# Nakuja_Remix_4.net
KiCad netlist of a schematic drawn in EasyEDA
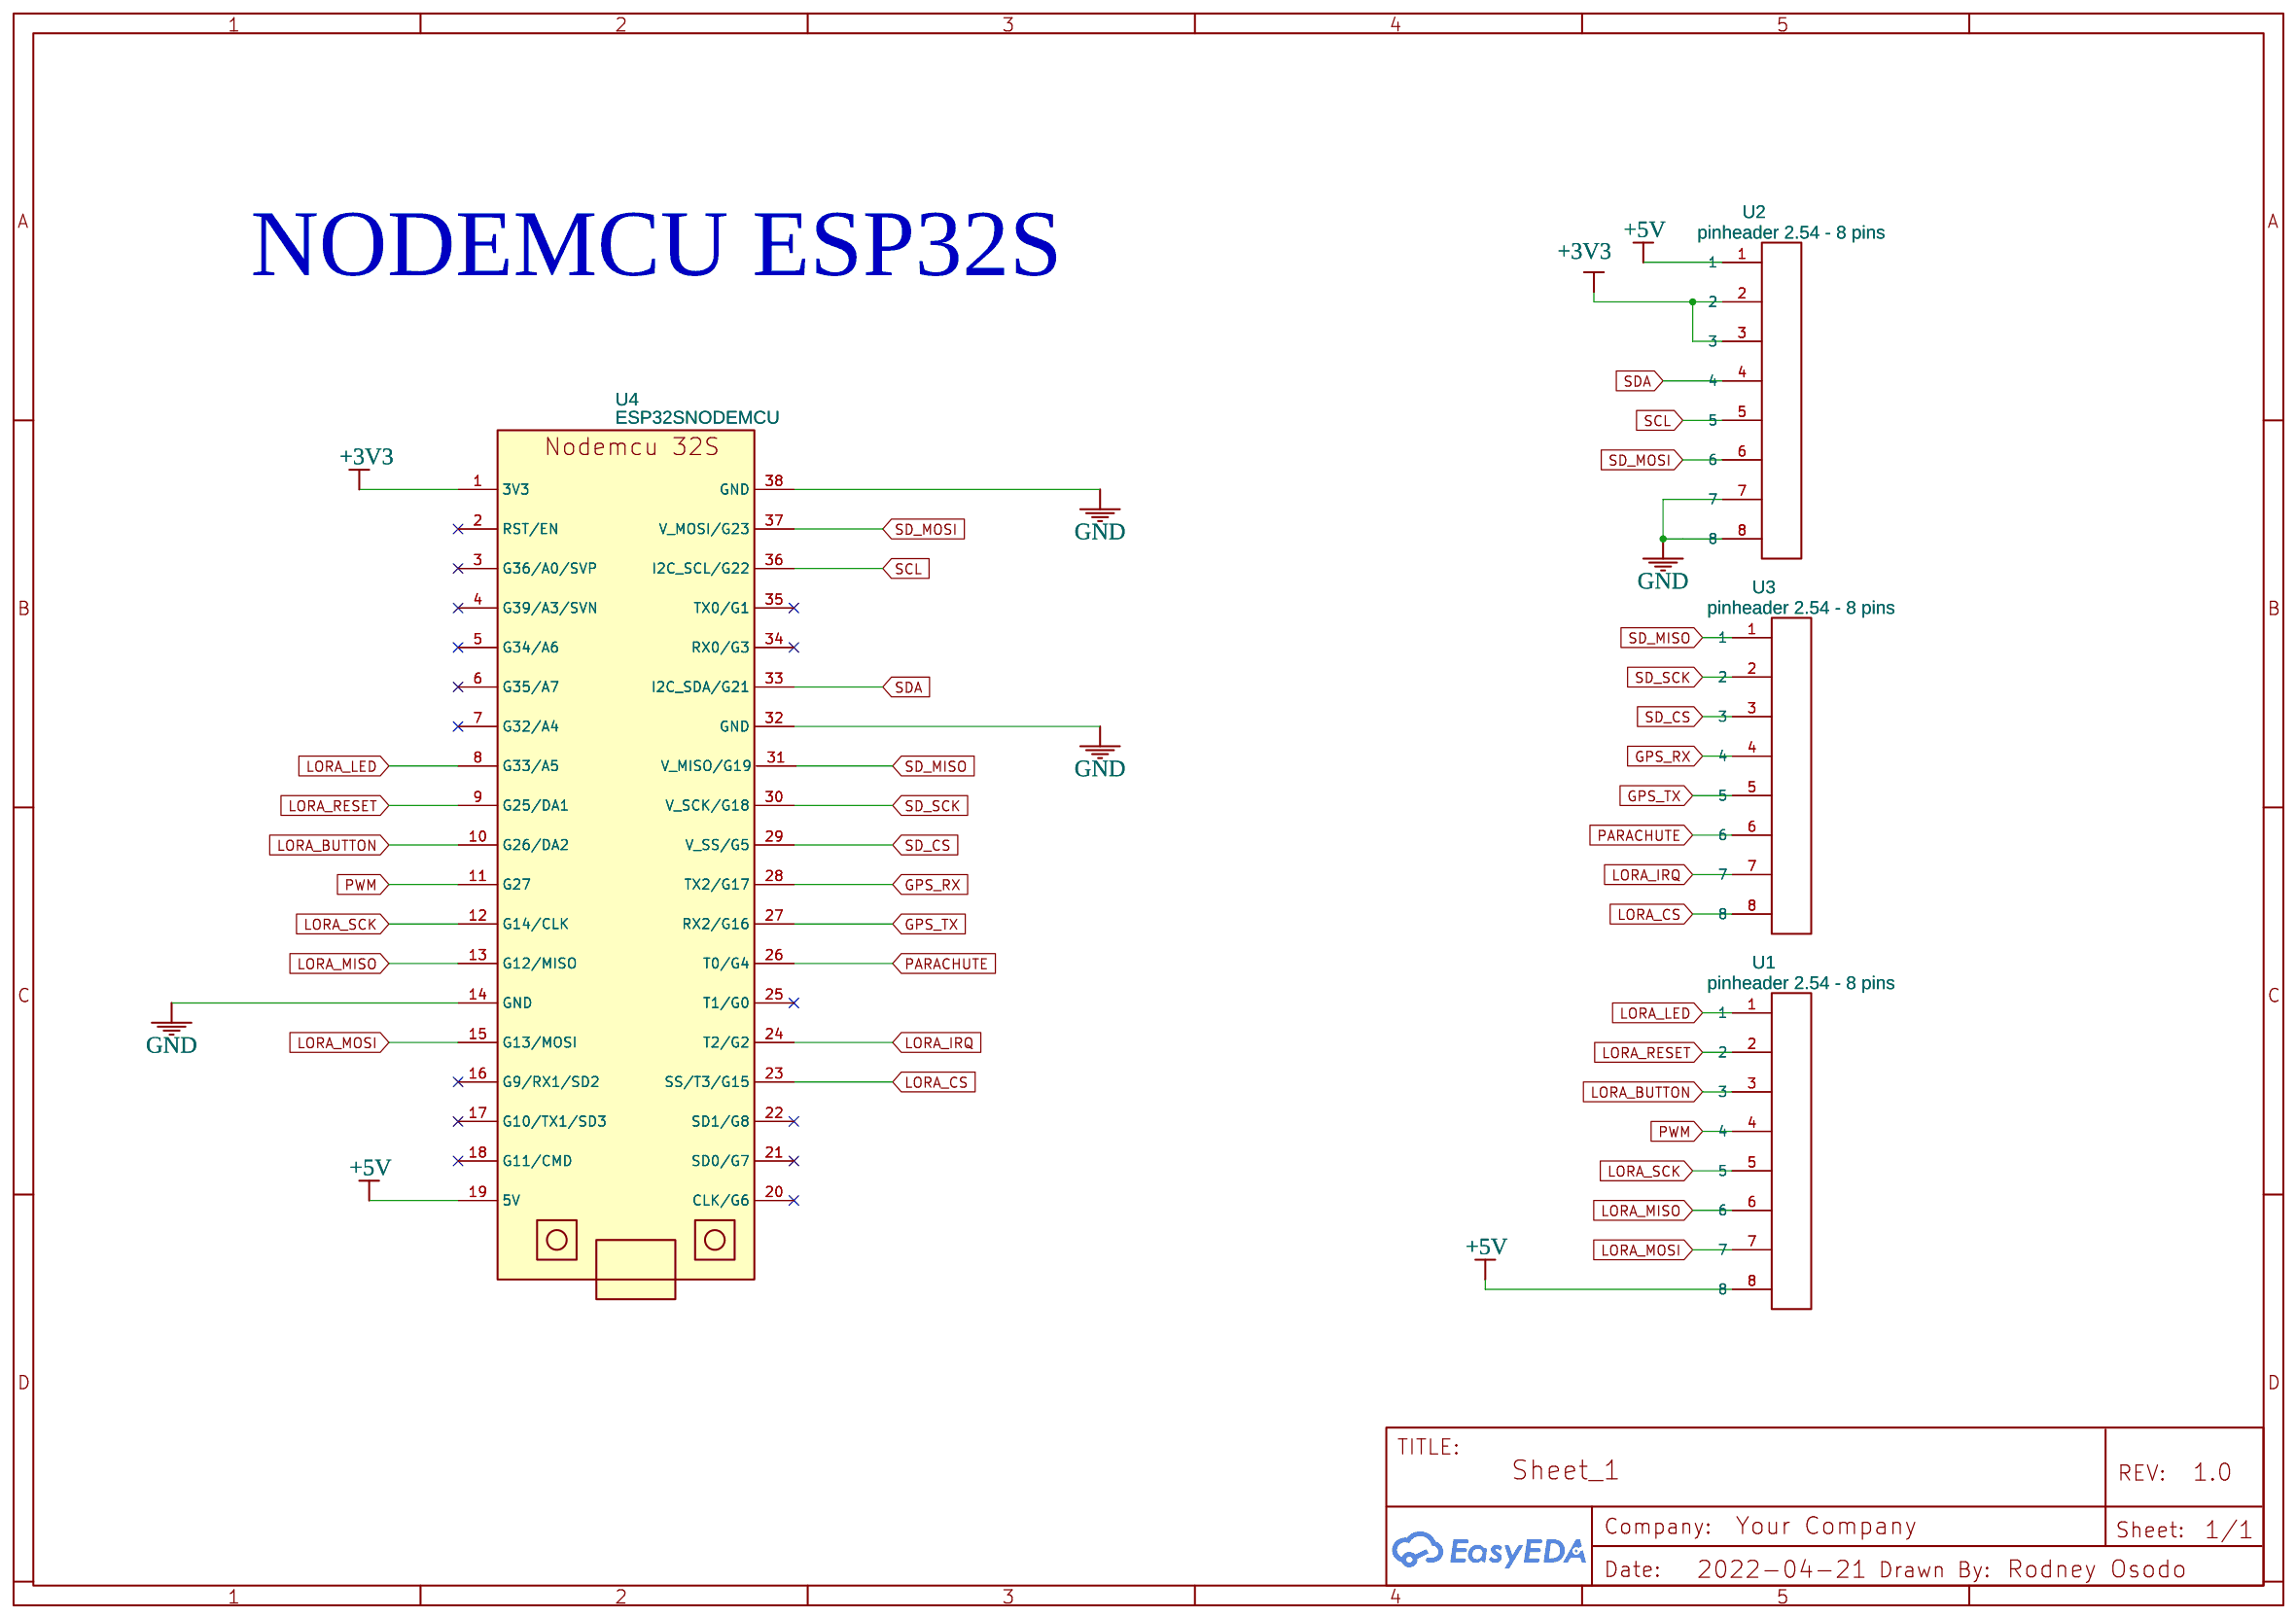
[diagram p0: schematic sheet]

(export (version "E")
  (design (tool "Eeschema 10.0.6"))
  (components
    (comp (ref "U1") (value "pinheader 2.54 - 8 pins") (libsource (lib "") (part "pinheader 2.54 - 8 pins")))
    (comp (ref "U2") (value "pinheader 2.54 - 8 pins") (libsource (lib "") (part "pinheader 2.54 - 8 pins")))
    (comp (ref "U3") (value "pinheader 2.54 - 8 pins") (libsource (lib "") (part "pinheader 2.54 - 8 pins")))
    (comp (ref "U4")
      (value "ESP32SNODEMCU")
      (fields (field (name "BOM_Manufacturer Part") "Nodemcu esp32"))
      (libsource (lib "") (part "ESP32SNODEMCU"))
    )
  )
  (nets
    (net (code "1") (name "+3V3") (class "Default")
      (node (ref "U2") (pin "2") (pinfunction "2_2") (pintype "unspecified"))
      (node (ref "U2") (pin "3") (pinfunction "3_3") (pintype "unspecified"))
      (node (ref "U4") (pin "1") (pinfunction "3V3_1") (pintype "passive"))
    )
    (net (code "2") (name "+5V") (class "Default")
      (node (ref "U1") (pin "8") (pinfunction "8_8") (pintype "unspecified"))
      (node (ref "U2") (pin "1") (pinfunction "1_1") (pintype "unspecified"))
      (node (ref "U4") (pin "19") (pinfunction "5V_19") (pintype "passive"))
    )
    (net (code "3") (name "GND") (class "Default")
      (node (ref "U2") (pin "7") (pinfunction "7_7") (pintype "unspecified"))
      (node (ref "U2") (pin "8") (pinfunction "8_8") (pintype "unspecified"))
      (node (ref "U4") (pin "14") (pinfunction "GND_14") (pintype "passive"))
      (node (ref "U4") (pin "32") (pinfunction "GND_32") (pintype "passive"))
      (node (ref "U4") (pin "38") (pinfunction "GND_38") (pintype "passive"))
    )
    (net (code "4") (name "GPS_RX") (class "Default")
      (node (ref "U3") (pin "4") (pinfunction "4_4") (pintype "unspecified"))
      (node (ref "U4") (pin "28") (pinfunction "TX2/G17_28") (pintype "bidirectional"))
    )
    (net (code "5") (name "GPS_TX") (class "Default")
      (node (ref "U3") (pin "5") (pinfunction "5_5") (pintype "unspecified"))
      (node (ref "U4") (pin "27") (pinfunction "RX2/G16_27") (pintype "bidirectional"))
    )
    (net (code "6") (name "LORA_BUTTON") (class "Default")
      (node (ref "U1") (pin "3") (pinfunction "3_3") (pintype "unspecified"))
      (node (ref "U4") (pin "10") (pinfunction "G26/DA2_10") (pintype "bidirectional"))
    )
    (net (code "7") (name "LORA_CS") (class "Default")
      (node (ref "U3") (pin "8") (pinfunction "8_8") (pintype "unspecified"))
      (node (ref "U4") (pin "23") (pinfunction "SS/T3/G15_23") (pintype "bidirectional"))
    )
    (net (code "8") (name "LORA_IRQ") (class "Default")
      (node (ref "U3") (pin "7") (pinfunction "7_7") (pintype "unspecified"))
      (node (ref "U4") (pin "24") (pinfunction "T2/G2_24") (pintype "bidirectional"))
    )
    (net (code "9") (name "LORA_LED") (class "Default")
      (node (ref "U1") (pin "1") (pinfunction "1_1") (pintype "unspecified"))
      (node (ref "U4") (pin "8") (pinfunction "G33/A5_8") (pintype "bidirectional"))
    )
    (net (code "10") (name "LORA_MISO") (class "Default")
      (node (ref "U1") (pin "6") (pinfunction "6_6") (pintype "unspecified"))
      (node (ref "U4") (pin "13") (pinfunction "G12/MISO_13") (pintype "bidirectional"))
    )
    (net (code "11") (name "LORA_MOSI") (class "Default")
      (node (ref "U1") (pin "7") (pinfunction "7_7") (pintype "unspecified"))
      (node (ref "U4") (pin "15") (pinfunction "G13/MOSI_15") (pintype "bidirectional"))
    )
    (net (code "12") (name "LORA_RESET") (class "Default")
      (node (ref "U1") (pin "2") (pinfunction "2_2") (pintype "unspecified"))
      (node (ref "U4") (pin "9") (pinfunction "G25/DA1_9") (pintype "bidirectional"))
    )
    (net (code "13") (name "LORA_SCK") (class "Default")
      (node (ref "U1") (pin "5") (pinfunction "5_5") (pintype "unspecified"))
      (node (ref "U4") (pin "12") (pinfunction "G14/CLK_12") (pintype "bidirectional"))
    )
    (net (code "14") (name "PARACHUTE") (class "Default")
      (node (ref "U3") (pin "6") (pinfunction "6_6") (pintype "unspecified"))
      (node (ref "U4") (pin "26") (pinfunction "T0/G4_26") (pintype "bidirectional"))
    )
    (net (code "15") (name "PWM") (class "Default")
      (node (ref "U1") (pin "4") (pinfunction "4_4") (pintype "unspecified"))
      (node (ref "U4") (pin "11") (pinfunction "G27_11") (pintype "bidirectional"))
    )
    (net (code "16") (name "SCL") (class "Default")
      (node (ref "U2") (pin "5") (pinfunction "5_5") (pintype "unspecified"))
      (node (ref "U4") (pin "36") (pinfunction "I2C_SCL/G22_36") (pintype "bidirectional"))
    )
    (net (code "17") (name "SDA") (class "Default")
      (node (ref "U2") (pin "4") (pinfunction "4_4") (pintype "unspecified"))
      (node (ref "U4") (pin "33") (pinfunction "I2C_SDA/G21_33") (pintype "bidirectional"))
    )
    (net (code "18") (name "SD_CS") (class "Default")
      (node (ref "U3") (pin "3") (pinfunction "3_3") (pintype "unspecified"))
      (node (ref "U4") (pin "29") (pinfunction "V_SS/G5_29") (pintype "bidirectional"))
    )
    (net (code "19") (name "SD_MISO") (class "Default")
      (node (ref "U3") (pin "1") (pinfunction "1_1") (pintype "unspecified"))
      (node (ref "U4") (pin "31") (pinfunction "V_MISO/G19_31") (pintype "bidirectional"))
    )
    (net (code "20") (name "SD_MOSI") (class "Default")
      (node (ref "U2") (pin "6") (pinfunction "6_6") (pintype "unspecified"))
      (node (ref "U4") (pin "37") (pinfunction "V_MOSI/G23_37") (pintype "bidirectional"))
    )
    (net (code "21") (name "SD_SCK") (class "Default")
      (node (ref "U3") (pin "2") (pinfunction "2_2") (pintype "unspecified"))
      (node (ref "U4") (pin "30") (pinfunction "V_SCK/G18_30") (pintype "bidirectional"))
    )
    (net (code "22") (name "unconnected-(U4-CLK{slash}G6-Pad20)") (class "Default")
      (node (ref "U4") (pin "20") (pinfunction "CLK/G6_20") (pintype "bidirectional+no_connect"))
    )
    (net (code "23") (name "unconnected-(U4-G9{slash}RX1{slash}SD2-Pad16)") (class "Default")
      (node (ref "U4") (pin "16") (pinfunction "G9/RX1/SD2_16") (pintype "bidirectional+no_connect"))
    )
    (net (code "24") (name "unconnected-(U4-G10{slash}TX1{slash}SD3-Pad17)") (class "Default")
      (node (ref "U4") (pin "17") (pinfunction "G10/TX1/SD3_17") (pintype "bidirectional+no_connect"))
    )
    (net (code "25") (name "unconnected-(U4-G11{slash}CMD-Pad18)") (class "Default")
      (node (ref "U4") (pin "18") (pinfunction "G11/CMD_18") (pintype "bidirectional+no_connect"))
    )
    (net (code "26") (name "unconnected-(U4-G32{slash}A4-Pad7)") (class "Default")
      (node (ref "U4") (pin "7") (pinfunction "G32/A4_7") (pintype "bidirectional+no_connect"))
    )
    (net (code "27") (name "unconnected-(U4-G34{slash}A6-Pad5)") (class "Default")
      (node (ref "U4") (pin "5") (pinfunction "G34/A6_5") (pintype "bidirectional+no_connect"))
    )
    (net (code "28") (name "unconnected-(U4-G35{slash}A7-Pad6)") (class "Default")
      (node (ref "U4") (pin "6") (pinfunction "G35/A7_6") (pintype "bidirectional+no_connect"))
    )
    (net (code "29") (name "unconnected-(U4-G36{slash}A0{slash}SVP-Pad3)") (class "Default")
      (node (ref "U4") (pin "3") (pinfunction "G36/A0/SVP_3") (pintype "bidirectional+no_connect"))
    )
    (net (code "30") (name "unconnected-(U4-G39{slash}A3{slash}SVN-Pad4)") (class "Default")
      (node (ref "U4") (pin "4") (pinfunction "G39/A3/SVN_4") (pintype "bidirectional+no_connect"))
    )
    (net (code "31") (name "unconnected-(U4-RST{slash}EN-Pad2)") (class "Default")
      (node (ref "U4") (pin "2") (pinfunction "RST/EN_2") (pintype "bidirectional+no_connect"))
    )
    (net (code "32") (name "unconnected-(U4-RX0{slash}G3-Pad34)") (class "Default")
      (node (ref "U4") (pin "34") (pinfunction "RX0/G3_34") (pintype "bidirectional+no_connect"))
    )
    (net (code "33") (name "unconnected-(U4-SD0{slash}G7-Pad21)") (class "Default")
      (node (ref "U4") (pin "21") (pinfunction "SD0/G7_21") (pintype "bidirectional+no_connect"))
    )
    (net (code "34") (name "unconnected-(U4-SD1{slash}G8-Pad22)") (class "Default")
      (node (ref "U4") (pin "22") (pinfunction "SD1/G8_22") (pintype "bidirectional+no_connect"))
    )
    (net (code "35") (name "unconnected-(U4-T1{slash}G0-Pad25)") (class "Default")
      (node (ref "U4") (pin "25") (pinfunction "T1/G0_25") (pintype "bidirectional+no_connect"))
    )
    (net (code "36") (name "unconnected-(U4-TX0{slash}G1-Pad35)") (class "Default")
      (node (ref "U4") (pin "35") (pinfunction "TX0/G1_35") (pintype "bidirectional+no_connect"))
    )
  )
)
